# Decap_Banks.net
KiCad netlist of a schematic drawn in Altium Designer
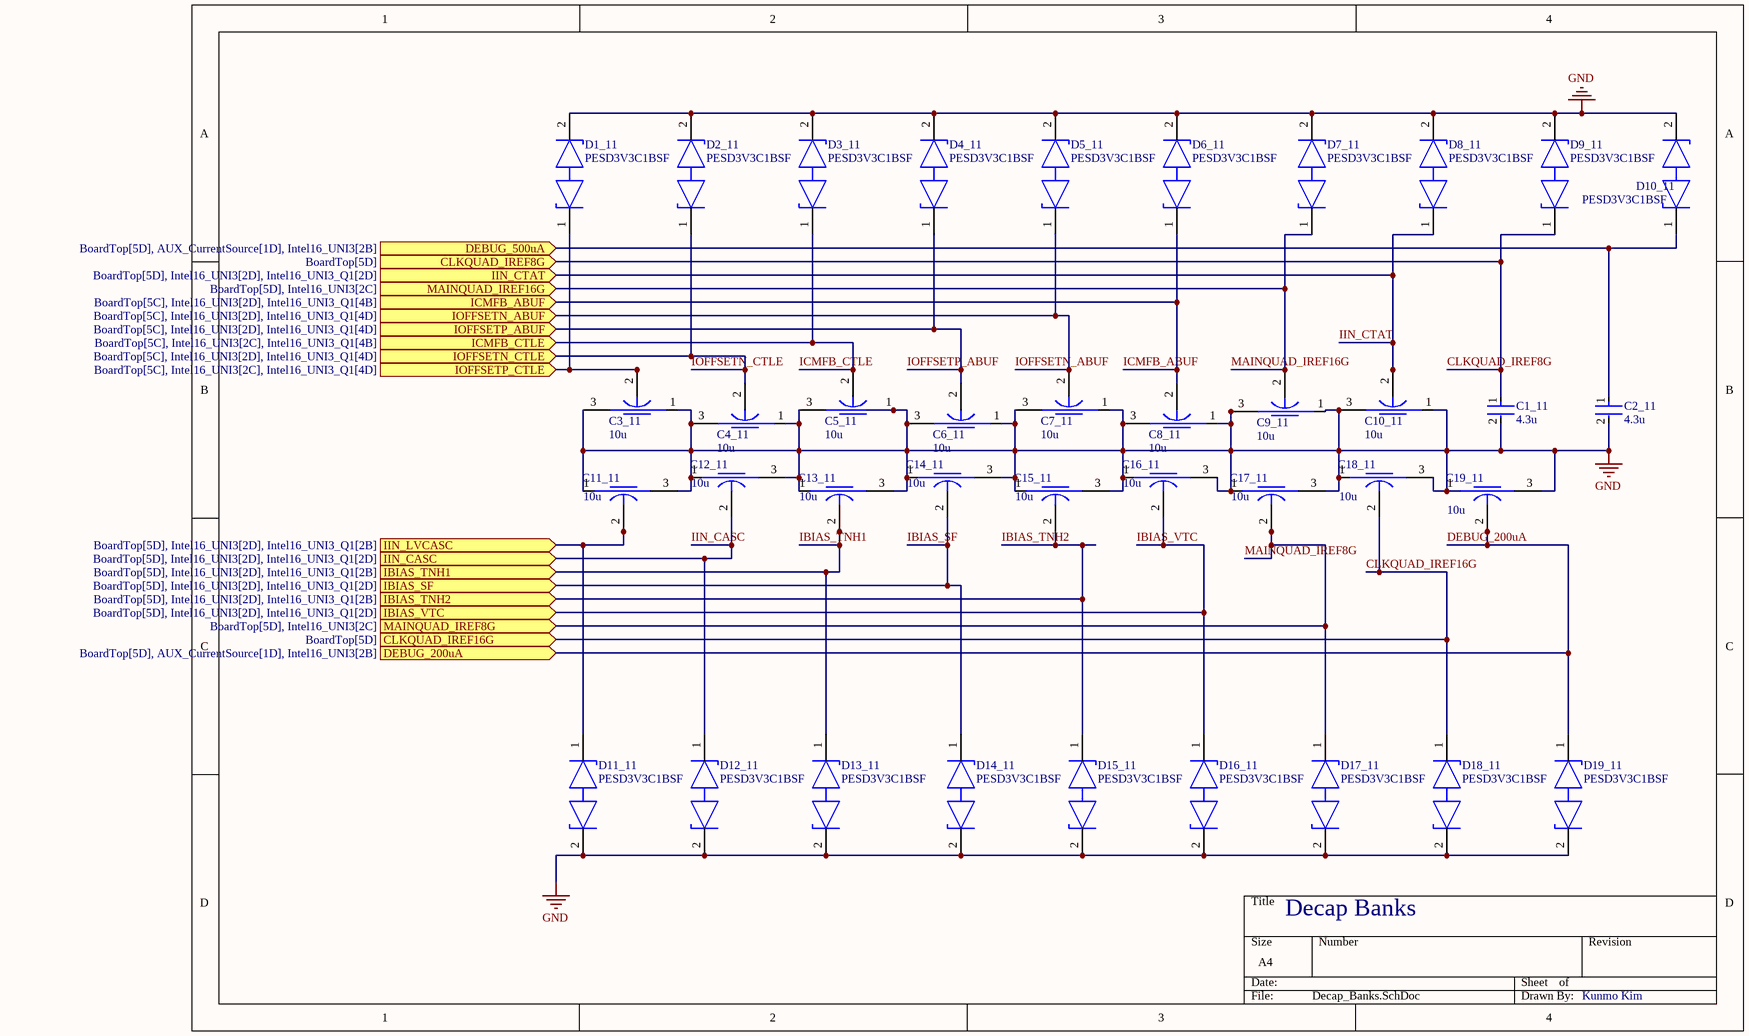
[diagram p0: Decap_Banks.SchDoc]

(export (version "E")
  (design (tool "Eeschema 10.0.6"))
  (components
    (comp (ref "C1_11")
      (value "4.3u")
      (footprint "FP-LLL1U4-0_05-IPC_C")
      (description "Cap Ceramic Monolithic 4.3uF 20% 4V X5R 15% 02404 (0610M)")
      (fields (field (name "TOLERANCE") "20%"))
      (libsource (lib "LLL_cap") (part "CMP-06035-061933-1"))
    )
    (comp (ref "C2_11")
      (value "4.3u")
      (footprint "FP-LLL1U4-0_05-IPC_C")
      (description "Cap Ceramic Monolithic 4.3uF 20% 4V X5R 15% 02404 (0610M)")
      (fields (field (name "TOLERANCE") "20%"))
      (libsource (lib "LLL_cap") (part "CMP-06035-061933-1"))
    )
    (comp (ref "C3_11")
      (value "10u")
      (footprint "FP-NFM15-0_2-MFG")
      (description "CAP FEEDTHRU")
      (libsource (lib "Altium Content Vault") (part "0d6e7657c98936515f4dd3c3b322889"))
    )
    (comp (ref "C4_11")
      (value "10u")
      (footprint "FP-NFM15-0_2-MFG")
      (description "CAP FEEDTHRU")
      (libsource (lib "Altium Content Vault") (part "0d6e7657c98936515f4dd3c3b322889"))
    )
    (comp (ref "C5_11")
      (value "10u")
      (footprint "FP-NFM15-0_2-MFG")
      (description "CAP FEEDTHRU")
      (libsource (lib "Altium Content Vault") (part "0d6e7657c98936515f4dd3c3b322889"))
    )
    (comp (ref "C6_11")
      (value "10u")
      (footprint "FP-NFM15-0_2-MFG")
      (description "CAP FEEDTHRU")
      (libsource (lib "Altium Content Vault") (part "0d6e7657c98936515f4dd3c3b322889"))
    )
    (comp (ref "C7_11")
      (value "10u")
      (footprint "FP-NFM15-0_2-MFG")
      (description "CAP FEEDTHRU")
      (libsource (lib "Altium Content Vault") (part "0d6e7657c98936515f4dd3c3b322889"))
    )
    (comp (ref "C8_11")
      (value "10u")
      (footprint "FP-NFM15-0_2-MFG")
      (description "CAP FEEDTHRU")
      (libsource (lib "Altium Content Vault") (part "0d6e7657c98936515f4dd3c3b322889"))
    )
    (comp (ref "C9_11")
      (value "10u")
      (footprint "FP-NFM15-0_2-MFG")
      (description "CAP FEEDTHRU")
      (libsource (lib "Altium Content Vault") (part "0d6e7657c98936515f4dd3c3b322889"))
    )
    (comp (ref "C10_11")
      (value "10u")
      (footprint "FP-NFM15-0_2-MFG")
      (description "CAP FEEDTHRU")
      (libsource (lib "Altium Content Vault") (part "0d6e7657c98936515f4dd3c3b322889"))
    )
    (comp (ref "C11_11")
      (value "10u")
      (footprint "FP-NFM15-0_2-MFG")
      (description "CAP FEEDTHRU")
      (libsource (lib "Altium Content Vault") (part "0d6e7657c98936515f4dd3c3b322889"))
    )
    (comp (ref "C12_11")
      (value "10u")
      (footprint "FP-NFM15-0_2-MFG")
      (description "CAP FEEDTHRU")
      (libsource (lib "Altium Content Vault") (part "0d6e7657c98936515f4dd3c3b322889"))
    )
    (comp (ref "C13_11")
      (value "10u")
      (footprint "FP-NFM15-0_2-MFG")
      (description "CAP FEEDTHRU")
      (libsource (lib "Altium Content Vault") (part "0d6e7657c98936515f4dd3c3b322889"))
    )
    (comp (ref "C14_11")
      (value "10u")
      (footprint "FP-NFM15-0_2-MFG")
      (description "CAP FEEDTHRU")
      (libsource (lib "Altium Content Vault") (part "0d6e7657c98936515f4dd3c3b322889"))
    )
    (comp (ref "C15_11")
      (value "10u")
      (footprint "FP-NFM15-0_2-MFG")
      (description "CAP FEEDTHRU")
      (libsource (lib "Altium Content Vault") (part "0d6e7657c98936515f4dd3c3b322889"))
    )
    (comp (ref "C16_11")
      (value "10u")
      (footprint "FP-NFM15-0_2-MFG")
      (description "CAP FEEDTHRU")
      (libsource (lib "Altium Content Vault") (part "0d6e7657c98936515f4dd3c3b322889"))
    )
    (comp (ref "C17_11")
      (value "10u")
      (footprint "FP-NFM15-0_2-MFG")
      (description "CAP FEEDTHRU")
      (libsource (lib "Altium Content Vault") (part "0d6e7657c98936515f4dd3c3b322889"))
    )
    (comp (ref "C18_11")
      (value "10u")
      (footprint "FP-NFM15-0_2-MFG")
      (description "CAP FEEDTHRU")
      (libsource (lib "Altium Content Vault") (part "0d6e7657c98936515f4dd3c3b322889"))
    )
    (comp (ref "C19_11")
      (value "10u")
      (footprint "FP-NFM15-0_2-MFG")
      (description "CAP FEEDTHRU")
      (libsource (lib "Altium Content Vault") (part "0d6e7657c98936515f4dd3c3b322889"))
    )
    (comp (ref "D1_11")
      (value "PESD3V3C1BSF")
      (footprint "FP-SOD962-2-MFG")
      (description "TVS DIODE 2VWM 3VC DSN0603-2")
      (libsource (lib "PESD2V0Y1BSFYL") (part "CMP-14436-000022-1"))
    )
    (comp (ref "D2_11")
      (value "PESD3V3C1BSF")
      (footprint "FP-SOD962-2-MFG")
      (description "TVS DIODE 2VWM 3VC DSN0603-2")
      (libsource (lib "PESD2V0Y1BSFYL") (part "CMP-14436-000022-1"))
    )
    (comp (ref "D3_11")
      (value "PESD3V3C1BSF")
      (footprint "FP-SOD962-2-MFG")
      (description "TVS DIODE 2VWM 3VC DSN0603-2")
      (libsource (lib "PESD2V0Y1BSFYL") (part "CMP-14436-000022-1"))
    )
    (comp (ref "D4_11")
      (value "PESD3V3C1BSF")
      (footprint "FP-SOD962-2-MFG")
      (description "TVS DIODE 2VWM 3VC DSN0603-2")
      (libsource (lib "PESD2V0Y1BSFYL") (part "CMP-14436-000022-1"))
    )
    (comp (ref "D5_11")
      (value "PESD3V3C1BSF")
      (footprint "FP-SOD962-2-MFG")
      (description "TVS DIODE 2VWM 3VC DSN0603-2")
      (libsource (lib "PESD2V0Y1BSFYL") (part "CMP-14436-000022-1"))
    )
    (comp (ref "D6_11")
      (value "PESD3V3C1BSF")
      (footprint "FP-SOD962-2-MFG")
      (description "TVS DIODE 2VWM 3VC DSN0603-2")
      (libsource (lib "PESD2V0Y1BSFYL") (part "CMP-14436-000022-1"))
    )
    (comp (ref "D7_11")
      (value "PESD3V3C1BSF")
      (footprint "FP-SOD962-2-MFG")
      (description "TVS DIODE 2VWM 3VC DSN0603-2")
      (libsource (lib "PESD2V0Y1BSFYL") (part "CMP-14436-000022-1"))
    )
    (comp (ref "D8_11")
      (value "PESD3V3C1BSF")
      (footprint "FP-SOD962-2-MFG")
      (description "TVS DIODE 2VWM 3VC DSN0603-2")
      (libsource (lib "PESD2V0Y1BSFYL") (part "CMP-14436-000022-1"))
    )
    (comp (ref "D9_11")
      (value "PESD3V3C1BSF")
      (footprint "FP-SOD962-2-MFG")
      (description "TVS DIODE 2VWM 3VC DSN0603-2")
      (libsource (lib "PESD2V0Y1BSFYL") (part "CMP-14436-000022-1"))
    )
    (comp (ref "D10_11")
      (value "PESD3V3C1BSF")
      (footprint "FP-SOD962-2-MFG")
      (description "TVS DIODE 2VWM 3VC DSN0603-2")
      (libsource (lib "PESD2V0Y1BSFYL") (part "CMP-14436-000022-1"))
    )
    (comp (ref "D11_11")
      (value "PESD3V3C1BSF")
      (footprint "FP-SOD962-2-MFG")
      (description "TVS DIODE 2VWM 3VC DSN0603-2")
      (libsource (lib "PESD2V0Y1BSFYL") (part "CMP-14436-000022-1"))
    )
    (comp (ref "D12_11")
      (value "PESD3V3C1BSF")
      (footprint "FP-SOD962-2-MFG")
      (description "TVS DIODE 2VWM 3VC DSN0603-2")
      (libsource (lib "PESD2V0Y1BSFYL") (part "CMP-14436-000022-1"))
    )
    (comp (ref "D13_11")
      (value "PESD3V3C1BSF")
      (footprint "FP-SOD962-2-MFG")
      (description "TVS DIODE 2VWM 3VC DSN0603-2")
      (libsource (lib "PESD2V0Y1BSFYL") (part "CMP-14436-000022-1"))
    )
    (comp (ref "D14_11")
      (value "PESD3V3C1BSF")
      (footprint "FP-SOD962-2-MFG")
      (description "TVS DIODE 2VWM 3VC DSN0603-2")
      (libsource (lib "PESD2V0Y1BSFYL") (part "CMP-14436-000022-1"))
    )
    (comp (ref "D15_11")
      (value "PESD3V3C1BSF")
      (footprint "FP-SOD962-2-MFG")
      (description "TVS DIODE 2VWM 3VC DSN0603-2")
      (libsource (lib "PESD2V0Y1BSFYL") (part "CMP-14436-000022-1"))
    )
    (comp (ref "D16_11")
      (value "PESD3V3C1BSF")
      (footprint "FP-SOD962-2-MFG")
      (description "TVS DIODE 2VWM 3VC DSN0603-2")
      (libsource (lib "PESD2V0Y1BSFYL") (part "CMP-14436-000022-1"))
    )
    (comp (ref "D17_11")
      (value "PESD3V3C1BSF")
      (footprint "FP-SOD962-2-MFG")
      (description "TVS DIODE 2VWM 3VC DSN0603-2")
      (libsource (lib "PESD2V0Y1BSFYL") (part "CMP-14436-000022-1"))
    )
    (comp (ref "D18_11")
      (value "PESD3V3C1BSF")
      (footprint "FP-SOD962-2-MFG")
      (description "TVS DIODE 2VWM 3VC DSN0603-2")
      (libsource (lib "PESD2V0Y1BSFYL") (part "CMP-14436-000022-1"))
    )
    (comp (ref "D19_11")
      (value "PESD3V3C1BSF")
      (footprint "FP-SOD962-2-MFG")
      (description "TVS DIODE 2VWM 3VC DSN0603-2")
      (libsource (lib "PESD2V0Y1BSFYL") (part "CMP-14436-000022-1"))
    )
  )
  (nets
    (net (code "1") (name "/CLKQUAD_IREF8G") (class "Default")
      (node (ref "C1_11") (pin "1") (pinfunction "1_1") (pintype "passive"))
      (node (ref "D9_11") (pin "1") (pinfunction "K1_1") (pintype "passive"))
    )
    (net (code "2") (name "/CLKQUAD_IREF16G") (class "Default")
      (node (ref "C18_11") (pin "2") (pinfunction "GND_2") (pintype "passive"))
      (node (ref "D18_11") (pin "1") (pinfunction "K1_1") (pintype "passive"))
    )
    (net (code "3") (name "/DEBUG_200uA") (class "Default")
      (node (ref "C19_11") (pin "2") (pinfunction "GND_2") (pintype "passive"))
      (node (ref "D19_11") (pin "1") (pinfunction "K1_1") (pintype "passive"))
    )
    (net (code "4") (name "/DEBUG_500uA") (class "Default")
      (node (ref "C2_11") (pin "1") (pinfunction "1_1") (pintype "passive"))
      (node (ref "D10_11") (pin "1") (pinfunction "K1_1") (pintype "passive"))
    )
    (net (code "5") (name "/IBIAS_SF") (class "Default")
      (node (ref "C14_11") (pin "2") (pinfunction "GND_2") (pintype "passive"))
      (node (ref "D14_11") (pin "1") (pinfunction "K1_1") (pintype "passive"))
    )
    (net (code "6") (name "/IBIAS_TNH1") (class "Default")
      (node (ref "C13_11") (pin "2") (pinfunction "GND_2") (pintype "passive"))
      (node (ref "D13_11") (pin "1") (pinfunction "K1_1") (pintype "passive"))
    )
    (net (code "7") (name "/IBIAS_TNH2") (class "Default")
      (node (ref "C15_11") (pin "2") (pinfunction "GND_2") (pintype "passive"))
      (node (ref "D15_11") (pin "1") (pinfunction "K1_1") (pintype "passive"))
    )
    (net (code "8") (name "/IBIAS_VTC") (class "Default")
      (node (ref "C16_11") (pin "2") (pinfunction "GND_2") (pintype "passive"))
      (node (ref "D16_11") (pin "1") (pinfunction "K1_1") (pintype "passive"))
    )
    (net (code "9") (name "/ICMFB_ABUF") (class "Default")
      (node (ref "C8_11") (pin "2") (pinfunction "GND_2") (pintype "passive"))
      (node (ref "D6_11") (pin "1") (pinfunction "K1_1") (pintype "passive"))
    )
    (net (code "10") (name "/ICMFB_CTLE") (class "Default")
      (node (ref "C5_11") (pin "2") (pinfunction "GND_2") (pintype "passive"))
      (node (ref "D3_11") (pin "1") (pinfunction "K1_1") (pintype "passive"))
    )
    (net (code "11") (name "/IIN_CASC") (class "Default")
      (node (ref "C12_11") (pin "2") (pinfunction "GND_2") (pintype "passive"))
      (node (ref "D12_11") (pin "1") (pinfunction "K1_1") (pintype "passive"))
    )
    (net (code "12") (name "/IIN_CTAT") (class "Default")
      (node (ref "C10_11") (pin "2") (pinfunction "GND_2") (pintype "passive"))
      (node (ref "D8_11") (pin "1") (pinfunction "K1_1") (pintype "passive"))
    )
    (net (code "13") (name "/IIN_LVCASC") (class "Default")
      (node (ref "C11_11") (pin "2") (pinfunction "GND_2") (pintype "passive"))
      (node (ref "D11_11") (pin "1") (pinfunction "K1_1") (pintype "passive"))
    )
    (net (code "14") (name "/IOFFSETN_ABUF") (class "Default")
      (node (ref "C7_11") (pin "2") (pinfunction "GND_2") (pintype "passive"))
      (node (ref "D5_11") (pin "1") (pinfunction "K1_1") (pintype "passive"))
    )
    (net (code "15") (name "/IOFFSETN_CTLE") (class "Default")
      (node (ref "C4_11") (pin "2") (pinfunction "GND_2") (pintype "passive"))
      (node (ref "D2_11") (pin "1") (pinfunction "K1_1") (pintype "passive"))
    )
    (net (code "16") (name "/IOFFSETP_ABUF") (class "Default")
      (node (ref "C6_11") (pin "2") (pinfunction "GND_2") (pintype "passive"))
      (node (ref "D4_11") (pin "1") (pinfunction "K1_1") (pintype "passive"))
    )
    (net (code "17") (name "/IOFFSETP_CTLE") (class "Default")
      (node (ref "C3_11") (pin "2") (pinfunction "GND_2") (pintype "passive"))
      (node (ref "D1_11") (pin "1") (pinfunction "K1_1") (pintype "passive"))
    )
    (net (code "18") (name "/MAINQUAD_IREF8G") (class "Default")
      (node (ref "C17_11") (pin "2") (pinfunction "GND_2") (pintype "passive"))
      (node (ref "D17_11") (pin "1") (pinfunction "K1_1") (pintype "passive"))
    )
    (net (code "19") (name "/MAINQUAD_IREF16G") (class "Default")
      (node (ref "C9_11") (pin "2") (pinfunction "GND_2") (pintype "passive"))
      (node (ref "D7_11") (pin "1") (pinfunction "K1_1") (pintype "passive"))
    )
    (net (code "20") (name "GND") (class "Default")
      (node (ref "C10_11") (pin "1") (pinfunction "Input_1") (pintype "passive"))
      (node (ref "C10_11") (pin "3") (pinfunction "Output_3") (pintype "passive"))
      (node (ref "C11_11") (pin "1") (pinfunction "Input_1") (pintype "passive"))
      (node (ref "C11_11") (pin "3") (pinfunction "Output_3") (pintype "passive"))
      (node (ref "C12_11") (pin "1") (pinfunction "Input_1") (pintype "passive"))
      (node (ref "C12_11") (pin "3") (pinfunction "Output_3") (pintype "passive"))
      (node (ref "C13_11") (pin "1") (pinfunction "Input_1") (pintype "passive"))
      (node (ref "C13_11") (pin "3") (pinfunction "Output_3") (pintype "passive"))
      (node (ref "C14_11") (pin "1") (pinfunction "Input_1") (pintype "passive"))
      (node (ref "C14_11") (pin "3") (pinfunction "Output_3") (pintype "passive"))
      (node (ref "C15_11") (pin "1") (pinfunction "Input_1") (pintype "passive"))
      (node (ref "C15_11") (pin "3") (pinfunction "Output_3") (pintype "passive"))
      (node (ref "C16_11") (pin "1") (pinfunction "Input_1") (pintype "passive"))
      (node (ref "C16_11") (pin "3") (pinfunction "Output_3") (pintype "passive"))
      (node (ref "C17_11") (pin "1") (pinfunction "Input_1") (pintype "passive"))
      (node (ref "C17_11") (pin "3") (pinfunction "Output_3") (pintype "passive"))
      (node (ref "C18_11") (pin "1") (pinfunction "Input_1") (pintype "passive"))
      (node (ref "C18_11") (pin "3") (pinfunction "Output_3") (pintype "passive"))
      (node (ref "C19_11") (pin "1") (pinfunction "Input_1") (pintype "passive"))
      (node (ref "C19_11") (pin "3") (pinfunction "Output_3") (pintype "passive"))
      (node (ref "C1_11") (pin "2") (pinfunction "2_2") (pintype "passive"))
      (node (ref "C2_11") (pin "2") (pinfunction "2_2") (pintype "passive"))
      (node (ref "C3_11") (pin "1") (pinfunction "Input_1") (pintype "passive"))
      (node (ref "C3_11") (pin "3") (pinfunction "Output_3") (pintype "passive"))
      (node (ref "C4_11") (pin "1") (pinfunction "Input_1") (pintype "passive"))
      (node (ref "C4_11") (pin "3") (pinfunction "Output_3") (pintype "passive"))
      (node (ref "C5_11") (pin "1") (pinfunction "Input_1") (pintype "passive"))
      (node (ref "C5_11") (pin "3") (pinfunction "Output_3") (pintype "passive"))
      (node (ref "C6_11") (pin "1") (pinfunction "Input_1") (pintype "passive"))
      (node (ref "C6_11") (pin "3") (pinfunction "Output_3") (pintype "passive"))
      (node (ref "C7_11") (pin "1") (pinfunction "Input_1") (pintype "passive"))
      (node (ref "C7_11") (pin "3") (pinfunction "Output_3") (pintype "passive"))
      (node (ref "C8_11") (pin "1") (pinfunction "Input_1") (pintype "passive"))
      (node (ref "C8_11") (pin "3") (pinfunction "Output_3") (pintype "passive"))
      (node (ref "C9_11") (pin "1") (pinfunction "Input_1") (pintype "passive"))
      (node (ref "C9_11") (pin "3") (pinfunction "Output_3") (pintype "passive"))
      (node (ref "D10_11") (pin "2") (pinfunction "K2_2") (pintype "passive"))
      (node (ref "D11_11") (pin "2") (pinfunction "K2_2") (pintype "passive"))
      (node (ref "D12_11") (pin "2") (pinfunction "K2_2") (pintype "passive"))
      (node (ref "D13_11") (pin "2") (pinfunction "K2_2") (pintype "passive"))
      (node (ref "D14_11") (pin "2") (pinfunction "K2_2") (pintype "passive"))
      (node (ref "D15_11") (pin "2") (pinfunction "K2_2") (pintype "passive"))
      (node (ref "D16_11") (pin "2") (pinfunction "K2_2") (pintype "passive"))
      (node (ref "D17_11") (pin "2") (pinfunction "K2_2") (pintype "passive"))
      (node (ref "D18_11") (pin "2") (pinfunction "K2_2") (pintype "passive"))
      (node (ref "D19_11") (pin "2") (pinfunction "K2_2") (pintype "passive"))
      (node (ref "D1_11") (pin "2") (pinfunction "K2_2") (pintype "passive"))
      (node (ref "D2_11") (pin "2") (pinfunction "K2_2") (pintype "passive"))
      (node (ref "D3_11") (pin "2") (pinfunction "K2_2") (pintype "passive"))
      (node (ref "D4_11") (pin "2") (pinfunction "K2_2") (pintype "passive"))
      (node (ref "D5_11") (pin "2") (pinfunction "K2_2") (pintype "passive"))
      (node (ref "D6_11") (pin "2") (pinfunction "K2_2") (pintype "passive"))
      (node (ref "D7_11") (pin "2") (pinfunction "K2_2") (pintype "passive"))
      (node (ref "D8_11") (pin "2") (pinfunction "K2_2") (pintype "passive"))
      (node (ref "D9_11") (pin "2") (pinfunction "K2_2") (pintype "passive"))
    )
  )
)
